# P10_USB_TO_UART0_IO_EXP_ADC.net
KiCad netlist of a schematic drawn in Altium Designer
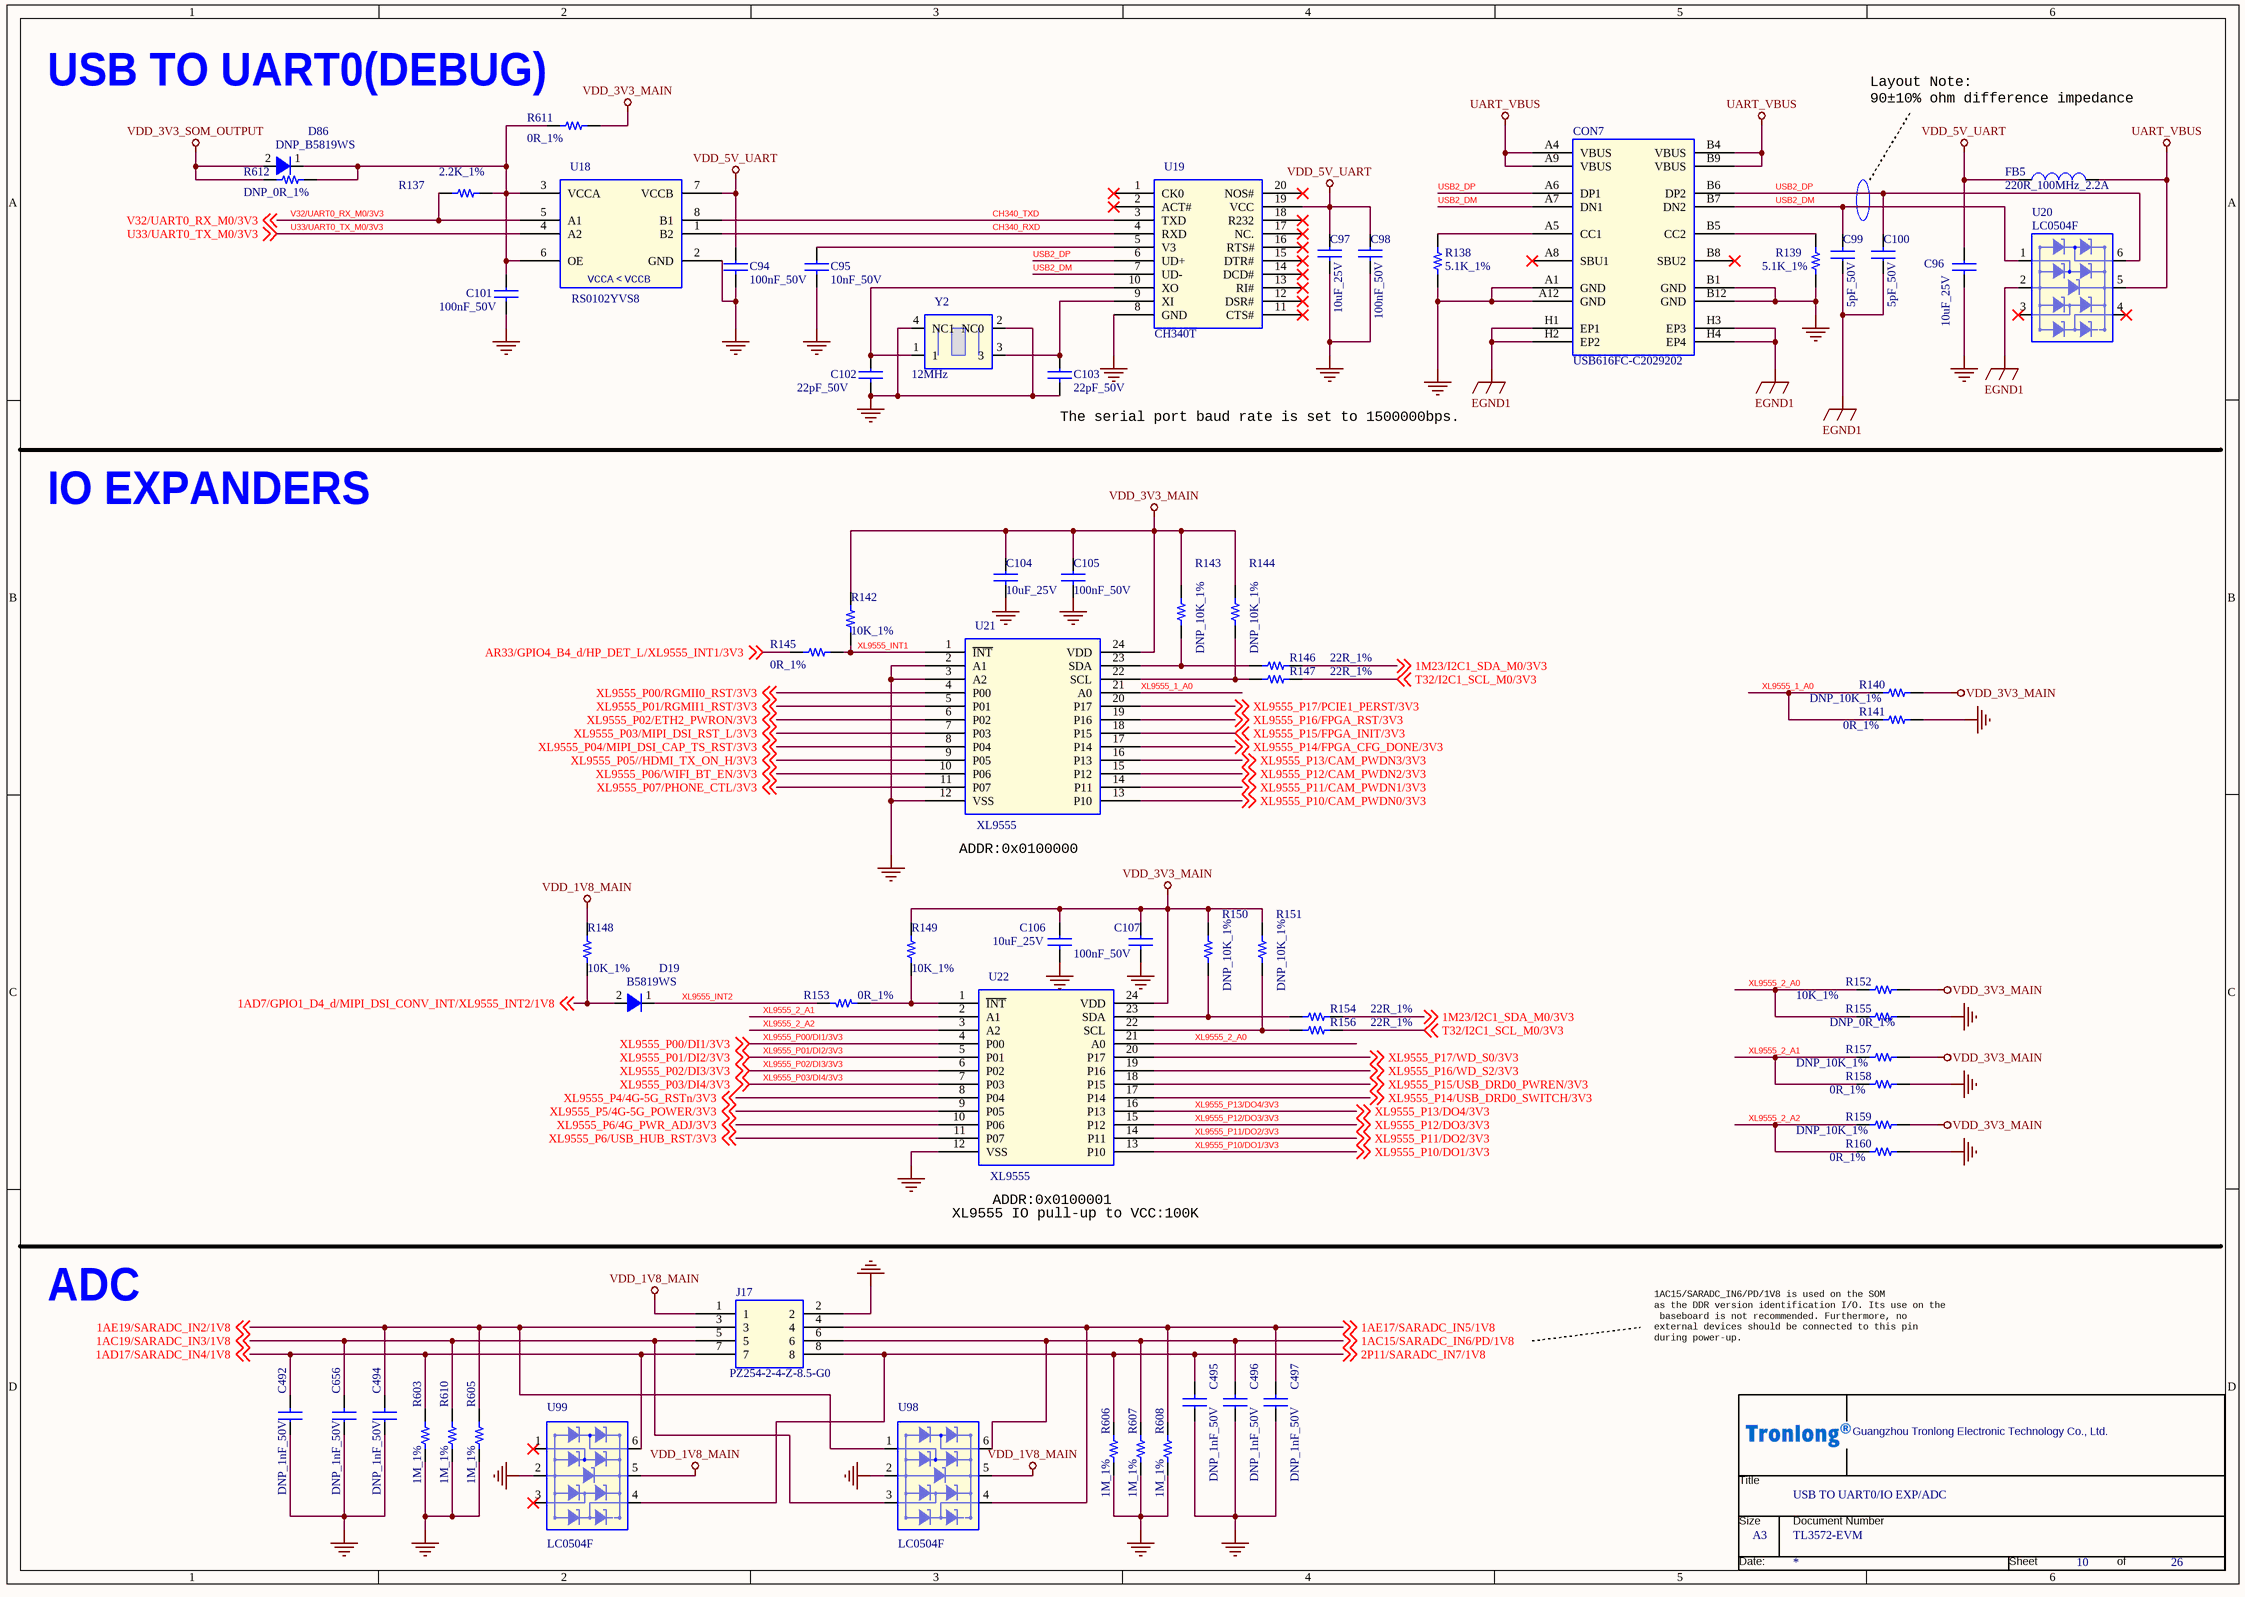
[diagram p0: P10_USB TO UART0_IO EXP_ADC.SchDoc]

(export (version "E")
  (design (tool "Eeschema 10.0.6"))
  (components
    (comp (ref "*")
      (value "Tronlong_TITTLE_20211115")
      (fields
        (field (name "DOC") "TL3572-EVM")
        (field (name "TITLE") "USB TO UART0/IO EXP/ADC")
        (field (name "ORGNAME") "Guangzhou Tronlong Electronic Technology Co., Ltd.")
        (field (name "PAGE SIZE") "A3")
        (field (name "PAGE NUMBER") "10")
        (field (name "PAGE COUNT") "26")
      )
      (libsource (lib "*") (part "Tronlong_TITTLE_20211115"))
    )
    (comp (ref "C94")
      (value "100nF_50V")
      (footprint "C0402")
      (description "贴片陶瓷电容,100nF,10%,50V,X7R")
      (fields
        (field (name "MANUFACTURER PARTNUMBER") "0402B104K500NT")
        (field (name "MANUFACTURER") "广东风华高新科技股份有限公司（FH）")
      )
      (libsource (lib "*") (part "CAP NP_Dup3"))
    )
    (comp (ref "C95")
      (value "10nF_50V")
      (footprint "C0402")
      (description "贴片陶瓷电容,10nF,10%,50V,X7R")
      (fields
        (field (name "MANUFACTURER PARTNUMBER") "0402B103K500NT")
        (field (name "MANUFACTURER") "广东风华高新科技股份有限公司（FH）")
      )
      (libsource (lib "*") (part "CAP NP_Dup3"))
    )
    (comp (ref "C96")
      (value "10uF_25V")
      (footprint "C0603")
      (description "贴片陶瓷电容,10uF,20%,25V,X5R")
      (fields
        (field (name "MANUFACTURER PARTNUMBER") "0603X106M250NT")
        (field (name "MANUFACTURER") "广东风华高新科技股份有限公司（FH）")
      )
      (libsource (lib "*") (part "CAP NP_Dup3"))
    )
    (comp (ref "C97")
      (value "10uF_25V")
      (footprint "C0603")
      (description "贴片陶瓷电容,10uF,20%,25V,X5R")
      (fields
        (field (name "MANUFACTURER") "广东风华高新科技股份有限公司（FH）")
        (field (name "MANUFACTURER PARTNUMBER") "0603X106M250NT")
      )
      (libsource (lib "*") (part "CAP NP_Dup3"))
    )
    (comp (ref "C98")
      (value "100nF_50V")
      (footprint "C0402")
      (description "贴片陶瓷电容,100nF,10%,50V,X7R")
      (fields
        (field (name "MANUFACTURER PARTNUMBER") "0402B104K500NT")
        (field (name "MANUFACTURER") "广东风华高新科技股份有限公司（FH）")
      )
      (libsource (lib "*") (part "CAP NP_Dup3"))
    )
    (comp (ref "C99")
      (value "5pF_50V")
      (footprint "C0402")
      (description "CC0402BRNPO9BN5R0")
      (fields
        (field (name "TOLERANCE") "±10%")
        (field (name "MANUFACTURER") "广州创龙")
        (field (name "CREATED BY") "JJJ")
      )
      (libsource (lib "*") (part "CAP NP_1"))
    )
    (comp (ref "C100")
      (value "5pF_50V")
      (footprint "C0402")
      (description "CC0402BRNPO9BN5R0")
      (fields
        (field (name "MANUFACTURER PARTNUMBER") "5pF,2%,C0402,50V,（NPO）")
        (field (name "MANUFACTURER") "广州创龙")
        (field (name "CREATED BY") "JJJ")
      )
      (libsource (lib "*") (part "CAP NP_1"))
    )
    (comp (ref "C101")
      (value "100nF_50V")
      (footprint "C0402")
      (description "贴片陶瓷电容,100nF,10%,50V,X7R")
      (fields
        (field (name "MANUFACTURER PARTNUMBER") "0402B104K500NT")
        (field (name "MANUFACTURER") "广东风华高新科技股份有限公司（FH）")
      )
      (libsource (lib "*") (part "CAP NP_Dup3"))
    )
    (comp (ref "C102")
      (value "22pF_50V")
      (footprint "C0603")
      (description "贴片陶瓷电容,22pF,5%,50V,COG")
      (fields
        (field (name "MANUFACTURER") "广东风华高新科技股份有限公司（FH）")
        (field (name "MANUFACTURER PARTNUMBER") "0603CG220J500NT")
      )
      (libsource (lib "*") (part "CAP NP_Dup3"))
    )
    (comp (ref "C103")
      (value "22pF_50V")
      (footprint "C0603")
      (description "贴片陶瓷电容,22pF,5%,50V,COG")
      (fields
        (field (name "MANUFACTURER") "广东风华高新科技股份有限公司（FH）")
        (field (name "MANUFACTURER PARTNUMBER") "0603CG220J500NT")
      )
      (libsource (lib "*") (part "CAP NP_Dup3"))
    )
    (comp (ref "C104")
      (value "10uF_25V")
      (footprint "C0603")
      (description "贴片陶瓷电容,4.7uF,10%,25V,X5R")
      (fields
        (field (name "MANUFACTURER") "广东风华高新科技股份有限公司（FH）")
        (field (name "MANUFACTURER PARTNUMBER") "0603X475K250NT")
      )
      (libsource (lib "*") (part "CAP NP_Dup3"))
    )
    (comp (ref "C105")
      (value "100nF_50V")
      (footprint "C0402")
      (description "贴片陶瓷电容,100nF,10%,50V,X7R")
      (fields
        (field (name "MANUFACTURER") "广东风华高新科技股份有限公司（FH）")
        (field (name "MANUFACTURER PARTNUMBER") "0402B104K500NT")
      )
      (libsource (lib "*") (part "CAP NP_Dup3"))
    )
    (comp (ref "C106")
      (value "10uF_25V")
      (footprint "C0603")
      (description "贴片陶瓷电容10uF,20%,25V,X5R")
      (fields
        (field (name "MANUFACTURER") "广东风华高新科技股份有限公司（FH）")
        (field (name "MANUFACTURER PARTNUMBER") "0603X106M250NT")
      )
      (libsource (lib "*") (part "CAP NP_Dup2"))
    )
    (comp (ref "C107")
      (value "100nF_50V")
      (footprint "C0402")
      (description "贴片陶瓷电容,100nF,10%,50V,X7R")
      (fields
        (field (name "MANUFACTURER PARTNUMBER") "0402B104K500NT")
        (field (name "MANUFACTURER") "广东风华高新科技股份有限公司（FH）")
      )
      (libsource (lib "*") (part "CAP NP_Dup2"))
    )
    (comp (ref "C492")
      (value "DNP_1nF_50V")
      (footprint "C0402")
      (description "贴片陶瓷电容,1nF,10%,50V,X7R")
      (fields
        (field (name "MANUFACTURER") "广东风华高新科技股份有限公司（FH）")
        (field (name "MANUFACTURER PARTNUMBER") "0402B102K500NT")
      )
      (libsource (lib "*") (part "CAP NP_Dup3"))
    )
    (comp (ref "C494")
      (value "DNP_1nF_50V")
      (footprint "C0402")
      (description "贴片陶瓷电容,1nF,10%,50V,X7R")
      (fields
        (field (name "MANUFACTURER") "广东风华高新科技股份有限公司（FH）")
        (field (name "MANUFACTURER PARTNUMBER") "0402B102K500NT")
      )
      (libsource (lib "*") (part "CAP NP_Dup3"))
    )
    (comp (ref "C495")
      (value "DNP_1nF_50V")
      (footprint "C0402")
      (description "贴片陶瓷电容,1nF,10%,50V,X7R")
      (fields
        (field (name "MANUFACTURER") "广东风华高新科技股份有限公司（FH）")
        (field (name "MANUFACTURER PARTNUMBER") "0402B102K500NT")
      )
      (libsource (lib "*") (part "CAP NP_Dup3"))
    )
    (comp (ref "C496")
      (value "DNP_1nF_50V")
      (footprint "C0402")
      (description "贴片陶瓷电容,1nF,10%,50V,X7R")
      (fields
        (field (name "MANUFACTURER") "广东风华高新科技股份有限公司（FH）")
        (field (name "MANUFACTURER PARTNUMBER") "0402B102K500NT")
      )
      (libsource (lib "*") (part "CAP NP_Dup3"))
    )
    (comp (ref "C497")
      (value "DNP_1nF_50V")
      (footprint "C0402")
      (description "贴片陶瓷电容,1nF,10%,50V,X7R")
      (fields
        (field (name "MANUFACTURER") "广东风华高新科技股份有限公司（FH）")
        (field (name "MANUFACTURER PARTNUMBER") "0402B102K500NT")
      )
      (libsource (lib "*") (part "CAP NP_Dup3"))
    )
    (comp (ref "C656")
      (value "DNP_1nF_50V")
      (footprint "C0402")
      (description "贴片陶瓷电容,1nF,10%,50V,X7R")
      (fields
        (field (name "PART NUMBER") "117-00-3036")
        (field (name "MANUFACTURER PARTNUMBER") "0402B102K500NT")
      )
      (libsource (lib "*") (part "CAP NP_Dup3"))
    )
    (comp (ref "CON7")
      (value "USB616FC-C2029202")
      (footprint "TYPE-C_16P_180_SMD")
      (description "Type-C座,16P,0.8mm,母座,侧贴")
      (fields (field (name "MANUFACTURER") "深圳市爱特姆科技有限公司（ATOM）"))
      (libsource (lib "*") (part "usb 3_0.0 type-c female"))
    )
    (comp (ref "D19")
      (value "B5819WS")
      (footprint "SOD-323")
      (description "肖特基二极管,VR=40V,IF=1A,VF=0.6V@1A")
      (fields (field (name "MFR") "On Semiconductor") (field (name "TIINTPARTNUMBER") "1E0013"))
      (libsource (lib "*") (part "Diode200mA250V_2"))
    )
    (comp (ref "D86")
      (value "DNP_B5819WS")
      (footprint "SOD-323")
      (description "肖特基二极管,VR=40V,IF=1A,VF=0.6V@1A")
      (fields (field (name "MFR") "On Semiconductor") (field (name "TIINTPARTNUMBER") "1E0013"))
      (libsource (lib "*") (part "Diode200mA250V_2"))
    )
    (comp (ref "FB5")
      (value "220R_100MHz_2.2A")
      (footprint "L0603")
      (description "磁珠,50mΩ,2.2A,220R@100MHz")
      (fields
        (field (name "MANUFACTURER") "深圳顺络电子股份有限公司（Sunlord）")
        (field (name "MANUFACTURER PARTNUMBER") "UPZ1608U221-2R2TF")
      )
      (libsource (lib "*") (part "FERRITE BEAD_0"))
    )
    (comp (ref "J17")
      (value "PZ254-2-4-Z-8.5-G0")
      (footprint "CON_2D54_2X4_TH")
      (description "插件双排排针,2x4P,2.54mm,针长L=11.5mm,180度")
      (fields (field (name "MANUFACTURER") "深圳市华灿天禄电子有限公司（HCTL)"))
      (libsource (lib "*") (part "PZ254-2-04-Z-8.5-G0"))
    )
    (comp (ref "R137")
      (value "2.2K_1%")
      (footprint "R0603")
      (description "贴片电阻,2.2K,±1%,1/10W")
      (fields
        (field (name "MANUFACTURER PARTNUMBER") "RS-03K2201FT")
        (field (name "MANUFACTURER") "广东风华高新科技股份有限公司（FH）")
      )
      (libsource (lib "*") (part "Resistor_Dup4"))
    )
    (comp (ref "R138")
      (value "5.1K_1%")
      (footprint "R0603")
      (description "RC0603FR-075K1L,0603WAF5101T5E")
      (fields
        (field (name "MANUFACTURER PARTNUMBER") "5.1K,±1%,R0603,≥1/10W")
        (field (name "MANUFACTURER") "广州创龙")
      )
      (libsource (lib "*") (part "Resistor_Dup4"))
    )
    (comp (ref "R139")
      (value "5.1K_1%")
      (footprint "R0603")
      (description "RC0603FR-075K1L,0603WAF5101T5E")
      (fields
        (field (name "MANUFACTURER") "广州创龙")
        (field (name "MANUFACTURER PARTNUMBER") "5.1K,±1%,R0603,≥1/10W")
      )
      (libsource (lib "*") (part "Resistor_Dup4"))
    )
    (comp (ref "R140")
      (value "DNP_10K_1%")
      (footprint "R0402")
      (description "贴片电阻,10K,±1%,1/16W")
      (fields
        (field (name "MANUFACTURER PARTNUMBER") "RC-02K1002FT")
        (field (name "MANUFACTURER") "广东风华高新科技股份有限公司（FH）")
      )
      (libsource (lib "*") (part "Resistor_Dup2"))
    )
    (comp (ref "R141")
      (value "0R_1%")
      (footprint "R0603")
      (description "贴片电阻,0R,±1%,1/10W")
      (fields
        (field (name "MANUFACTURER") "广东风华高新科技股份有限公司（FH）")
        (field (name "MANUFACTURER PARTNUMBER") "RS-03000FT")
      )
      (libsource (lib "*") (part "Resistor_Dup2"))
    )
    (comp (ref "R142")
      (value "10K_1%")
      (footprint "R0402")
      (description "贴片电阻,10K,±1%,1/16W")
      (fields
        (field (name "MANUFACTURER PARTNUMBER") "RC-02K1002FT")
        (field (name "MANUFACTURER") "广东风华高新科技股份有限公司（FH）")
      )
      (libsource (lib "*") (part "Resistor_Dup2"))
    )
    (comp (ref "R143")
      (value "DNP_10K_1%")
      (footprint "R0402")
      (description "贴片电阻,10K,±1%,1/16W")
      (fields
        (field (name "MANUFACTURER") "广东风华高新科技股份有限公司（FH）")
        (field (name "MANUFACTURER PARTNUMBER") "RC-02K1002FT")
      )
      (libsource (lib "*") (part "Resistor_Dup2"))
    )
    (comp (ref "R144")
      (value "DNP_10K_1%")
      (footprint "R0402")
      (description "贴片电阻,10K,±1%,1/16W")
      (fields
        (field (name "MANUFACTURER") "广东风华高新科技股份有限公司（FH）")
        (field (name "MANUFACTURER PARTNUMBER") "RC-02K1002FT")
      )
      (libsource (lib "*") (part "Resistor_Dup2"))
    )
    (comp (ref "R145")
      (value "0R_1%")
      (footprint "R0402")
      (description "贴片电阻,0R,±1%,1/16W")
      (fields
        (field (name "MANUFACTURER") "广东风华高新科技股份有限公司（FH）")
        (field (name "MANUFACTURER PARTNUMBER") "RC-02000FT")
      )
      (libsource (lib "*") (part "Resistor_Dup2"))
    )
    (comp (ref "R146")
      (value "22R_1%")
      (footprint "R0402")
      (description "贴片电阻,22R,±1%,1/16W")
      (fields
        (field (name "MANUFACTURER PARTNUMBER") "RC-02K22R0FT")
        (field (name "MANUFACTURER") "广东风华高新科技股份有限公司（FH）")
      )
      (libsource (lib "*") (part "Resistor_Dup2"))
    )
    (comp (ref "R147")
      (value "22R_1%")
      (footprint "R0402")
      (description "贴片电阻,22R,±1%,1/16W")
      (fields
        (field (name "MANUFACTURER PARTNUMBER") "RC-02K22R0FT")
        (field (name "MANUFACTURER") "广东风华高新科技股份有限公司（FH）")
      )
      (libsource (lib "*") (part "Resistor_Dup2"))
    )
    (comp (ref "R148")
      (value "10K_1%")
      (footprint "R0402")
      (description "贴片电阻,10K,±1%,1/16W")
      (fields
        (field (name "MANUFACTURER PARTNUMBER") "RC-02K1002FT")
        (field (name "MANUFACTURER") "广东风华高新科技股份有限公司（FH）")
      )
      (libsource (lib "*") (part "Resistor"))
    )
    (comp (ref "R149")
      (value "10K_1%")
      (footprint "R0402")
      (description "贴片电阻,10K,±1%,1/16W")
      (fields
        (field (name "MANUFACTURER PARTNUMBER") "RC-02K1002FT")
        (field (name "MANUFACTURER") "广东风华高新科技股份有限公司（FH）")
      )
      (libsource (lib "*") (part "Resistor"))
    )
    (comp (ref "R150")
      (value "DNP_10K_1%")
      (footprint "R0402")
      (description "贴片电阻,10K,±1%,1/16W")
      (fields
        (field (name "MANUFACTURER PARTNUMBER") "RC-02K1002FT")
        (field (name "MANUFACTURER") "广东风华高新科技股份有限公司（FH）")
      )
      (libsource (lib "*") (part "Resistor"))
    )
    (comp (ref "R151")
      (value "DNP_10K_1%")
      (footprint "R0402")
      (description "贴片电阻,10K,±1%,1/16W")
      (fields
        (field (name "MANUFACTURER") "广东风华高新科技股份有限公司（FH）")
        (field (name "MANUFACTURER PARTNUMBER") "RC-02K1002FT")
      )
      (libsource (lib "*") (part "Resistor"))
    )
    (comp (ref "R152")
      (value "10K_1%")
      (footprint "R0402")
      (description "贴片电阻,10K,±1%,1/16W")
      (fields
        (field (name "MANUFACTURER PARTNUMBER") "RC-02K1002FT")
        (field (name "MANUFACTURER") "广东风华高新科技股份有限公司（FH）")
      )
      (libsource (lib "*") (part "Resistor"))
    )
    (comp (ref "R153")
      (value "0R_1%")
      (footprint "R0402")
      (description "贴片电阻,0R,±1%,1/16W")
      (fields
        (field (name "MANUFACTURER") "广东风华高新科技股份有限公司（FH）")
        (field (name "MANUFACTURER PARTNUMBER") "RC-02000FT")
      )
      (libsource (lib "*") (part "Resistor"))
    )
    (comp (ref "R154")
      (value "22R_1%")
      (footprint "R0402")
      (description "贴片电阻,22R,±1%,1/16W")
      (fields
        (field (name "MANUFACTURER") "广东风华高新科技股份有限公司（FH）")
        (field (name "MANUFACTURER PARTNUMBER") "RC-02K22R0FT")
      )
      (libsource (lib "*") (part "Resistor"))
    )
    (comp (ref "R155")
      (value "DNP_0R_1%")
      (footprint "R0402")
      (description "贴片电阻,0R,±1%,1/16W")
      (fields
        (field (name "MANUFACTURER PARTNUMBER") "RC-02000FT")
        (field (name "MANUFACTURER") "广东风华高新科技股份有限公司（FH）")
      )
      (libsource (lib "*") (part "Resistor"))
    )
    (comp (ref "R156")
      (value "22R_1%")
      (footprint "R0402")
      (description "贴片电阻,22R,±1%,1/16W")
      (fields
        (field (name "MANUFACTURER") "广东风华高新科技股份有限公司（FH）")
        (field (name "MANUFACTURER PARTNUMBER") "RC-02K22R0FT")
      )
      (libsource (lib "*") (part "Resistor"))
    )
    (comp (ref "R157")
      (value "DNP_10K_1%")
      (footprint "R0402")
      (description "贴片电阻,10K,±1%,1/16W")
      (fields
        (field (name "MANUFACTURER PARTNUMBER") "RC-02K1002FT")
        (field (name "MANUFACTURER") "广东风华高新科技股份有限公司（FH）")
      )
      (libsource (lib "*") (part "Resistor"))
    )
    (comp (ref "R158")
      (value "0R_1%")
      (footprint "R0402")
      (description "贴片电阻,0R,±1%,1/16W")
      (fields
        (field (name "MANUFACTURER PARTNUMBER") "RC-02000FT")
        (field (name "MANUFACTURER") "广东风华高新科技股份有限公司（FH）")
      )
      (libsource (lib "*") (part "Resistor"))
    )
    (comp (ref "R159")
      (value "DNP_10K_1%")
      (footprint "R0402")
      (description "贴片电阻,10K,±1%,1/16W")
      (fields
        (field (name "MANUFACTURER PARTNUMBER") "RC-02K1002FT")
        (field (name "MANUFACTURER") "广东风华高新科技股份有限公司（FH）")
      )
      (libsource (lib "*") (part "Resistor"))
    )
    (comp (ref "R160")
      (value "0R_1%")
      (footprint "R0402")
      (description "贴片电阻,0R,±1%,1/16W")
      (fields
        (field (name "MANUFACTURER PARTNUMBER") "RC-02000FT")
        (field (name "MANUFACTURER") "广东风华高新科技股份有限公司（FH）")
      )
      (libsource (lib "*") (part "Resistor"))
    )
    (comp (ref "R603")
      (value "1M_1%")
      (footprint "R0603")
      (description "贴片电阻,1M,±1%,1/10W")
      (fields
        (field (name "MANUFACTURER PARTNUMBER") "RS-03K1004FT")
        (field (name "MANUFACTURER") "广东风华高新科技股份有限公司（FH）")
      )
      (libsource (lib "*") (part "Resistor_Dup3"))
    )
    (comp (ref "R605")
      (value "1M_1%")
      (footprint "R0603")
      (description "贴片电阻,1M,±1%,1/10W")
      (fields
        (field (name "MANUFACTURER PARTNUMBER") "RS-03K1004FT")
        (field (name "MANUFACTURER") "广东风华高新科技股份有限公司（FH）")
      )
      (libsource (lib "*") (part "Resistor_Dup3"))
    )
    (comp (ref "R606")
      (value "1M_1%")
      (footprint "R0603")
      (description "贴片电阻,1M,±1%,1/10W")
      (fields
        (field (name "MANUFACTURER") "广东风华高新科技股份有限公司（FH）")
        (field (name "MANUFACTURER PARTNUMBER") "RS-03K1004FT")
      )
      (libsource (lib "*") (part "Resistor_Dup3"))
    )
    (comp (ref "R607")
      (value "1M_1%")
      (footprint "R0603")
      (description "贴片电阻,1M,±1%,1/10W")
      (fields
        (field (name "MANUFACTURER PARTNUMBER") "RS-03K1004FT")
        (field (name "MANUFACTURER") "广东风华高新科技股份有限公司（FH）")
      )
      (libsource (lib "*") (part "Resistor_Dup3"))
    )
    (comp (ref "R608")
      (value "1M_1%")
      (footprint "R0603")
      (description "贴片电阻,1M,±1%,1/10W")
      (fields
        (field (name "MANUFACTURER") "广东风华高新科技股份有限公司（FH）")
        (field (name "MANUFACTURER PARTNUMBER") "RS-03K1004FT")
      )
      (libsource (lib "*") (part "Resistor_Dup3"))
    )
    (comp (ref "R610")
      (value "1M_1%")
      (footprint "R0603")
      (description "贴片电阻,1M,±1%,1/10W")
      (fields
        (field (name "MANUFACTURER PARTNUMBER") "RS-03K1004FT")
        (field (name "MANUFACTURER") "广东风华高新科技股份有限公司（FH）")
      )
      (libsource (lib "*") (part "Resistor_Dup3"))
    )
    (comp (ref "R611")
      (value "0R_1%")
      (footprint "R0402")
      (description "贴片电阻,0R,±1%,1/16W")
      (fields
        (field (name "MANUFACTURER PARTNUMBER") "RC-02000FT")
        (field (name "MANUFACTURER") "广东风华高新科技股份有限公司（FH）")
      )
      (libsource (lib "*") (part "Resistor_Dup2"))
    )
    (comp (ref "R612")
      (value "DNP_0R_1%")
      (footprint "R0402")
      (description "贴片电阻,0R,±1%,1/16W")
      (fields
        (field (name "MANUFACTURER PARTNUMBER") "RC-02000FT")
        (field (name "MANUFACTURER") "广东风华高新科技股份有限公司（FH）")
      )
      (libsource (lib "*") (part "Resistor_Dup2"))
    )
    (comp (ref "U18")
      (value "RS0102YVS8")
      (footprint "SOP8-20-91")
      (description "2位双向电平转换器")
      (fields (field (name "MANUFACTURER") "江苏润石科技有限公司（RUNIC）"))
      (libsource (lib "*") (part "TXS0102DCUR_0"))
    )
    (comp (ref "U19")
      (value "CH340T")
      (footprint "TSSOP-20")
      (description "USB转UART芯片")
      (fields (field (name "MANUFACTURER") "南京沁恒微电子股份有限公司（WCH）"))
      (libsource (lib "*") (part "CH340T"))
    )
    (comp (ref "U20")
      (value "LC0504F")
      (footprint "SOT363")
      (description "ESD二极管,VRWM=5V,VBR=6V,四组,单向,8KV,15KV")
      (fields (field (name "MANUFACTURER") "上海雷卯电子科技有限公司（Leiditech）"))
      (libsource (lib "*") (part "PRTR5V0U4Y"))
    )
    (comp (ref "U21")
      (value "XL9555")
      (footprint "TSSOP24")
      (description "拓展IO芯片")
      (fields (field (name "MANUFACTURER") "信路达信息技术（厦门）有限（xinluda）"))
      (libsource (lib "*") (part "XL9555_0"))
    )
    (comp (ref "U22")
      (value "XL9555")
      (footprint "TSSOP24")
      (description "拓展IO芯片")
      (fields (field (name "MANUFACTURER") "信路达信息技术（厦门）有限公司（xinluda）"))
      (libsource (lib "*") (part "XL9555_0"))
    )
    (comp (ref "U98")
      (value "LC0504F")
      (footprint "SOT363")
      (description "ESD二极管,VRWM=5V,VBR=6V,四组,单向,8KV,15KV")
      (fields (field (name "MANUFACTURER") "上海雷卯电子科技有限公司（Leiditech）"))
      (libsource (lib "*") (part "PRTR5V0U4Y"))
    )
    (comp (ref "U99")
      (value "LC0504F")
      (footprint "SOT363")
      (description "ESD二极管,VRWM=5V,VBR=6V,四组,单向,8KV,15KV")
      (fields (field (name "MANUFACTURER") "上海雷卯电子科技有限公司（Leiditech）"))
      (libsource (lib "*") (part "PRTR5V0U4Y"))
    )
    (comp (ref "Y2")
      (value "12MHz")
      (footprint "SMD_3225")
      (description "四脚无源晶振,12MHz,±10ppm,12pF,100Ω,±30ppm")
      (fields
        (field (name "MANUFACTURER") "深圳市星通时频电子有限公司（SCTF）")
        (field (name "MANUFACTURER PARTNUMBER") "S3B12.000F1210F30")
      )
      (libsource (lib "*") (part "CRYSTAL"))
    )
  )
  (nets
    (net (code "1") (name "/CH340_RXD") (class "Default")
      (node (ref "U18") (pin "1") (pinfunction "B2_1") (pintype "passive"))
      (node (ref "U19") (pin "4") (pinfunction "RXD_4") (pintype "passive"))
    )
    (net (code "2") (name "/CH340_TXD") (class "Default")
      (node (ref "U18") (pin "8") (pinfunction "B1_8") (pintype "passive"))
      (node (ref "U19") (pin "3") (pinfunction "TXD_3") (pintype "passive"))
    )
    (net (code "3") (name "/USB2_DM") (class "Default")
      (node (ref "C99") (pin "2") (pinfunction "2_2") (pintype "passive"))
      (node (ref "CON7") (pin "A7") (pinfunction "DN1_A7") (pintype "passive"))
      (node (ref "CON7") (pin "B7") (pinfunction "DN2_B7") (pintype "passive"))
      (node (ref "U19") (pin "7") (pinfunction "UD-_7") (pintype "passive"))
      (node (ref "U20") (pin "1") (pinfunction "1_1") (pintype "passive"))
    )
    (net (code "4") (name "/USB2_DP") (class "Default")
      (node (ref "C100") (pin "2") (pinfunction "2_2") (pintype "passive"))
      (node (ref "CON7") (pin "A6") (pinfunction "DP1_A6") (pintype "passive"))
      (node (ref "CON7") (pin "B6") (pinfunction "DP2_B6") (pintype "passive"))
      (node (ref "U19") (pin "6") (pinfunction "UD+_6") (pintype "passive"))
      (node (ref "U20") (pin "6") (pinfunction "6_6") (pintype "passive"))
    )
    (net (code "5") (name "/XL9555_1_A0") (class "Default")
      (node (ref "R140") (pin "2") (pinfunction "2_2") (pintype "passive"))
      (node (ref "R141") (pin "1") (pinfunction "1_1") (pintype "passive"))
      (node (ref "U21") (pin "21") (pinfunction "A0_21") (pintype "passive"))
    )
    (net (code "6") (name "/XL9555_2_A0") (class "Default")
      (node (ref "R152") (pin "2") (pinfunction "2_2") (pintype "passive"))
      (node (ref "R155") (pin "1") (pinfunction "1_1") (pintype "passive"))
      (node (ref "U22") (pin "21") (pinfunction "A0_21") (pintype "passive"))
    )
    (net (code "7") (name "/XL9555_2_A1") (class "Default")
      (node (ref "R157") (pin "2") (pinfunction "2_2") (pintype "passive"))
      (node (ref "R158") (pin "1") (pinfunction "1_1") (pintype "passive"))
      (node (ref "U22") (pin "2") (pinfunction "A1_2") (pintype "passive"))
    )
    (net (code "8") (name "/XL9555_2_A2") (class "Default")
      (node (ref "R159") (pin "2") (pinfunction "2_2") (pintype "passive"))
      (node (ref "R160") (pin "1") (pinfunction "1_1") (pintype "passive"))
      (node (ref "U22") (pin "3") (pinfunction "A2_3") (pintype "passive"))
    )
    (net (code "9") (name "/XL9555_INT1") (class "Default")
      (node (ref "R142") (pin "2") (pinfunction "2_2") (pintype "passive"))
      (node (ref "R145") (pin "2") (pinfunction "2_2") (pintype "passive"))
      (node (ref "U21") (pin "1") (pinfunction "~{INT}_1") (pintype "passive"))
    )
    (net (code "10") (name "/XL9555_INT2") (class "Default")
      (node (ref "D19") (pin "1") (pinfunction "Anode_1") (pintype "passive"))
      (node (ref "R153") (pin "1") (pinfunction "1_1") (pintype "passive"))
    )
    (net (code "11") (name "1AC15{slash}SARADC_IN6{slash}PD{slash}1V8") (class "Default")
      (node (ref "C496") (pin "2") (pinfunction "2_2") (pintype "passive"))
      (node (ref "J17") (pin "6") (pinfunction "6_6") (pintype "passive"))
      (node (ref "R607") (pin "1") (pinfunction "1_1") (pintype "passive"))
      (node (ref "U98") (pin "6") (pinfunction "6_6") (pintype "passive"))
    )
    (net (code "12") (name "1AC19{slash}SARADC_IN3{slash}1V8") (class "Default")
      (node (ref "C656") (pin "2") (pinfunction "2_2") (pintype "passive"))
      (node (ref "J17") (pin "5") (pinfunction "5_5") (pintype "passive"))
      (node (ref "R610") (pin "1") (pinfunction "1_1") (pintype "passive"))
      (node (ref "U98") (pin "3") (pinfunction "3_3") (pintype "passive"))
    )
    (net (code "13") (name "1AD7{slash}GPIO1_D4_d{slash}MIPI_DSI_CONV_INT{slash}XL9555_INT2{slash}1V8") (class "Default")
      (node (ref "D19") (pin "2") (pinfunction "Cathode_2") (pintype "passive"))
      (node (ref "R148") (pin "2") (pinfunction "2_2") (pintype "passive"))
    )
    (net (code "14") (name "1AD17{slash}SARADC_IN4{slash}1V8") (class "Default")
      (node (ref "C492") (pin "2") (pinfunction "2_2") (pintype "passive"))
      (node (ref "J17") (pin "7") (pinfunction "7_7") (pintype "passive"))
      (node (ref "R603") (pin "1") (pinfunction "1_1") (pintype "passive"))
      (node (ref "U99") (pin "6") (pinfunction "6_6") (pintype "passive"))
    )
    (net (code "15") (name "1AE17{slash}SARADC_IN5{slash}1V8") (class "Default")
      (node (ref "C497") (pin "2") (pinfunction "2_2") (pintype "passive"))
      (node (ref "J17") (pin "4") (pinfunction "4_4") (pintype "passive"))
      (node (ref "R608") (pin "1") (pinfunction "1_1") (pintype "passive"))
      (node (ref "U98") (pin "4") (pinfunction "4_4") (pintype "passive"))
    )
    (net (code "16") (name "1AE19{slash}SARADC_IN2{slash}1V8") (class "Default")
      (node (ref "C494") (pin "2") (pinfunction "2_2") (pintype "passive"))
      (node (ref "J17") (pin "3") (pinfunction "3_3") (pintype "passive"))
      (node (ref "R605") (pin "1") (pinfunction "1_1") (pintype "passive"))
      (node (ref "U98") (pin "1") (pinfunction "1_1") (pintype "passive"))
    )
    (net (code "17") (name "1M23{slash}I2C1_SDA_M0{slash}3V3") (class "Default")
      (node (ref "R146") (pin "1") (pinfunction "1_1") (pintype "passive"))
      (node (ref "R154") (pin "1") (pinfunction "1_1") (pintype "passive"))
    )
    (net (code "18") (name "2P11{slash}SARADC_IN7{slash}1V8") (class "Default")
      (node (ref "C495") (pin "2") (pinfunction "2_2") (pintype "passive"))
      (node (ref "J17") (pin "8") (pinfunction "8_8") (pintype "passive"))
      (node (ref "R606") (pin "1") (pinfunction "1_1") (pintype "passive"))
      (node (ref "U99") (pin "4") (pinfunction "4_4") (pintype "passive"))
    )
    (net (code "19") (name "AR33{slash}GPIO4_B4_d{slash}HP_DET_L{slash}XL9555_INT1{slash}3V3") (class "Default")
      (node (ref "R145") (pin "1") (pinfunction "1_1") (pintype "passive"))
    )
    (net (code "20") (name "EGND1") (class "Default")
      (node (ref "C100") (pin "1") (pinfunction "1_1") (pintype "passive"))
      (node (ref "C99") (pin "1") (pinfunction "1_1") (pintype "passive"))
      (node (ref "CON7") (pin "H1") (pinfunction "EP1_H1") (pintype "power_in"))
      (node (ref "CON7") (pin "H2") (pinfunction "EP2_H2") (pintype "power_in"))
      (node (ref "CON7") (pin "H3") (pinfunction "EP3_H3") (pintype "power_in"))
      (node (ref "CON7") (pin "H4") (pinfunction "EP4_H4") (pintype "power_in"))
      (node (ref "U20") (pin "2") (pinfunction "2_2") (pintype "passive"))
    )
    (net (code "21") (name "GND") (class "Default")
      (node (ref "C101") (pin "2") (pinfunction "2_2") (pintype "passive"))
      (node (ref "C102") (pin "2") (pinfunction "2_2") (pintype "passive"))
      (node (ref "C103") (pin "2") (pinfunction "2_2") (pintype "passive"))
      (node (ref "C104") (pin "2") (pinfunction "2_2") (pintype "passive"))
      (node (ref "C105") (pin "2") (pinfunction "2_2") (pintype "passive"))
      (node (ref "C106") (pin "2") (pinfunction "2_2") (pintype "passive"))
      (node (ref "C107") (pin "2") (pinfunction "2_2") (pintype "passive"))
      (node (ref "C492") (pin "1") (pinfunction "1_1") (pintype "passive"))
      (node (ref "C494") (pin "1") (pinfunction "1_1") (pintype "passive"))
      (node (ref "C495") (pin "1") (pinfunction "1_1") (pintype "passive"))
      (node (ref "C496") (pin "1") (pinfunction "1_1") (pintype "passive"))
      (node (ref "C497") (pin "1") (pinfunction "1_1") (pintype "passive"))
      (node (ref "C656") (pin "1") (pinfunction "1_1") (pintype "passive"))
      (node (ref "C94") (pin "2") (pinfunction "2_2") (pintype "passive"))
      (node (ref "C95") (pin "2") (pinfunction "2_2") (pintype "passive"))
      (node (ref "C96") (pin "2") (pinfunction "2_2") (pintype "passive"))
      (node (ref "C97") (pin "2") (pinfunction "2_2") (pintype "passive"))
      (node (ref "C98") (pin "2") (pinfunction "2_2") (pintype "passive"))
      (node (ref "CON7") (pin "A1") (pinfunction "GND_A1") (pintype "power_in"))
      (node (ref "CON7") (pin "A12") (pinfunction "GND_A12") (pintype "power_in"))
      (node (ref "CON7") (pin "B1") (pinfunction "GND_B1") (pintype "power_in"))
      (node (ref "CON7") (pin "B12") (pinfunction "GND_B12") (pintype "power_in"))
      (node (ref "J17") (pin "2") (pinfunction "2_2") (pintype "passive"))
      (node (ref "R138") (pin "2") (pinfunction "2_2") (pintype "passive"))
      (node (ref "R139") (pin "2") (pinfunction "2_2") (pintype "passive"))
      (node (ref "R141") (pin "2") (pinfunction "2_2") (pintype "passive"))
      (node (ref "R155") (pin "2") (pinfunction "2_2") (pintype "passive"))
      (node (ref "R158") (pin "2") (pinfunction "2_2") (pintype "passive"))
      (node (ref "R160") (pin "2") (pinfunction "2_2") (pintype "passive"))
      (node (ref "R603") (pin "2") (pinfunction "2_2") (pintype "passive"))
      (node (ref "R605") (pin "2") (pinfunction "2_2") (pintype "passive"))
      (node (ref "R606") (pin "2") (pinfunction "2_2") (pintype "passive"))
      (node (ref "R607") (pin "2") (pinfunction "2_2") (pintype "passive"))
      (node (ref "R608") (pin "2") (pinfunction "2_2") (pintype "passive"))
      (node (ref "R610") (pin "2") (pinfunction "2_2") (pintype "passive"))
      (node (ref "U18") (pin "2") (pinfunction "GND_2") (pintype "passive"))
      (node (ref "U19") (pin "8") (pinfunction "GND_8") (pintype "passive"))
      (node (ref "U21") (pin "12") (pinfunction "VSS_12") (pintype "passive"))
      (node (ref "U21") (pin "2") (pinfunction "A1_2") (pintype "passive"))
      (node (ref "U21") (pin "3") (pinfunction "A2_3") (pintype "passive"))
      (node (ref "U22") (pin "12") (pinfunction "VSS_12") (pintype "passive"))
      (node (ref "U98") (pin "2") (pinfunction "2_2") (pintype "passive"))
      (node (ref "U99") (pin "2") (pinfunction "2_2") (pintype "passive"))
      (node (ref "Y2") (pin "2") (pinfunction "NC0_2") (pintype "passive"))
      (node (ref "Y2") (pin "4") (pinfunction "NC1_4") (pintype "passive"))
    )
    (net (code "22") (name "Net-(CON7-CC1)") (class "Default")
      (node (ref "CON7") (pin "A5") (pinfunction "CC1_A5") (pintype "passive"))
      (node (ref "R138") (pin "1") (pinfunction "1_1") (pintype "passive"))
    )
    (net (code "23") (name "Net-(CON7-CC2)") (class "Default")
      (node (ref "CON7") (pin "B5") (pinfunction "CC2_B5") (pintype "passive"))
      (node (ref "R139") (pin "1") (pinfunction "1_1") (pintype "passive"))
    )
    (net (code "24") (name "Net-(D86-Anode)") (class "Default")
      (node (ref "C101") (pin "1") (pinfunction "1_1") (pintype "passive"))
      (node (ref "D86") (pin "1") (pinfunction "Anode_1") (pintype "passive"))
      (node (ref "R137") (pin "2") (pinfunction "2_2") (pintype "passive"))
      (node (ref "R611") (pin "1") (pinfunction "1_1") (pintype "passive"))
      (node (ref "R612") (pin "2") (pinfunction "2_2") (pintype "passive"))
      (node (ref "U18") (pin "3") (pinfunction "VCCA_3") (pintype "passive"))
      (node (ref "U18") (pin "6") (pinfunction "OE_6") (pintype "passive"))
    )
    (net (code "25") (name "Net-(U19-V3)") (class "Default")
      (node (ref "C95") (pin "1") (pinfunction "1_1") (pintype "passive"))
      (node (ref "U19") (pin "5") (pinfunction "V3_5") (pintype "passive"))
    )
    (net (code "26") (name "Net-(U19-XI)") (class "Default")
      (node (ref "C103") (pin "1") (pinfunction "1_1") (pintype "passive"))
      (node (ref "U19") (pin "9") (pinfunction "XI_9") (pintype "passive"))
      (node (ref "Y2") (pin "3") (pinfunction "3_3") (pintype "passive"))
    )
    (net (code "27") (name "Net-(U19-XO)") (class "Default")
      (node (ref "C102") (pin "1") (pinfunction "1_1") (pintype "passive"))
      (node (ref "U19") (pin "10") (pinfunction "XO_10") (pintype "passive"))
      (node (ref "Y2") (pin "1") (pinfunction "1_1") (pintype "passive"))
    )
    (net (code "28") (name "Net-(U21-SCL)") (class "Default")
      (node (ref "R144") (pin "2") (pinfunction "2_2") (pintype "passive"))
      (node (ref "R147") (pin "2") (pinfunction "2_2") (pintype "passive"))
      (node (ref "U21") (pin "22") (pinfunction "SCL_22") (pintype "passive"))
    )
    (net (code "29") (name "Net-(U21-SDA)") (class "Default")
      (node (ref "R143") (pin "2") (pinfunction "2_2") (pintype "passive"))
      (node (ref "R146") (pin "2") (pinfunction "2_2") (pintype "passive"))
      (node (ref "U21") (pin "23") (pinfunction "SDA_23") (pintype "passive"))
    )
    (net (code "30") (name "Net-(U22-SCL)") (class "Default")
      (node (ref "R151") (pin "2") (pinfunction "2_2") (pintype "passive"))
      (node (ref "R156") (pin "2") (pinfunction "2_2") (pintype "passive"))
      (node (ref "U22") (pin "22") (pinfunction "SCL_22") (pintype "passive"))
    )
    (net (code "31") (name "Net-(U22-SDA)") (class "Default")
      (node (ref "R150") (pin "2") (pinfunction "2_2") (pintype "passive"))
      (node (ref "R154") (pin "2") (pinfunction "2_2") (pintype "passive"))
      (node (ref "U22") (pin "23") (pinfunction "SDA_23") (pintype "passive"))
    )
    (net (code "32") (name "Net-(U22-~{INT})") (class "Default")
      (node (ref "R149") (pin "2") (pinfunction "2_2") (pintype "passive"))
      (node (ref "R153") (pin "2") (pinfunction "2_2") (pintype "passive"))
      (node (ref "U22") (pin "1") (pinfunction "~{INT}_1") (pintype "passive"))
    )
    (net (code "33") (name "T32{slash}I2C1_SCL_M0{slash}3V3") (class "Default")
      (node (ref "R147") (pin "1") (pinfunction "1_1") (pintype "passive"))
      (node (ref "R156") (pin "1") (pinfunction "1_1") (pintype "passive"))
    )
    (net (code "34") (name "U33{slash}UART0_TX_M0{slash}3V3") (class "Default")
      (node (ref "U18") (pin "4") (pinfunction "A2_4") (pintype "passive"))
    )
    (net (code "35") (name "UART_VBUS") (class "Default")
      (node (ref "CON7") (pin "A4") (pinfunction "VBUS_A4") (pintype "power_in"))
      (node (ref "CON7") (pin "A9") (pinfunction "VBUS_A9") (pintype "power_in"))
      (node (ref "CON7") (pin "B4") (pinfunction "VBUS_B4") (pintype "power_in"))
      (node (ref "CON7") (pin "B9") (pinfunction "VBUS_B9") (pintype "power_in"))
      (node (ref "FB5") (pin "2") (pinfunction "2_2") (pintype "passive"))
      (node (ref "U20") (pin "5") (pinfunction "5_5") (pintype "passive"))
    )
    (net (code "36") (name "V32{slash}UART0_RX_M0{slash}3V3") (class "Default")
      (node (ref "R137") (pin "1") (pinfunction "1_1") (pintype "passive"))
      (node (ref "U18") (pin "5") (pinfunction "A1_5") (pintype "passive"))
    )
    (net (code "37") (name "VDD_1V8_MAIN") (class "Default")
      (node (ref "J17") (pin "1") (pinfunction "1_1") (pintype "passive"))
      (node (ref "R148") (pin "1") (pinfunction "1_1") (pintype "passive"))
      (node (ref "U98") (pin "5") (pinfunction "5_5") (pintype "passive"))
      (node (ref "U99") (pin "5") (pinfunction "5_5") (pintype "passive"))
    )
    (net (code "38") (name "VDD_3V3_MAIN") (class "Default")
      (node (ref "C104") (pin "1") (pinfunction "1_1") (pintype "passive"))
      (node (ref "C105") (pin "1") (pinfunction "1_1") (pintype "passive"))
      (node (ref "C106") (pin "1") (pinfunction "1_1") (pintype "passive"))
      (node (ref "C107") (pin "1") (pinfunction "1_1") (pintype "passive"))
      (node (ref "R140") (pin "1") (pinfunction "1_1") (pintype "passive"))
      (node (ref "R142") (pin "1") (pinfunction "1_1") (pintype "passive"))
      (node (ref "R143") (pin "1") (pinfunction "1_1") (pintype "passive"))
      (node (ref "R144") (pin "1") (pinfunction "1_1") (pintype "passive"))
      (node (ref "R149") (pin "1") (pinfunction "1_1") (pintype "passive"))
      (node (ref "R150") (pin "1") (pinfunction "1_1") (pintype "passive"))
      (node (ref "R151") (pin "1") (pinfunction "1_1") (pintype "passive"))
      (node (ref "R152") (pin "1") (pinfunction "1_1") (pintype "passive"))
      (node (ref "R157") (pin "1") (pinfunction "1_1") (pintype "passive"))
      (node (ref "R159") (pin "1") (pinfunction "1_1") (pintype "passive"))
      (node (ref "R611") (pin "2") (pinfunction "2_2") (pintype "passive"))
      (node (ref "U21") (pin "24") (pinfunction "VDD_24") (pintype "passive"))
      (node (ref "U22") (pin "24") (pinfunction "VDD_24") (pintype "passive"))
    )
    (net (code "39") (name "VDD_3V3_SOM_OUTPUT") (class "Default")
      (node (ref "D86") (pin "2") (pinfunction "Cathode_2") (pintype "passive"))
      (node (ref "R612") (pin "1") (pinfunction "1_1") (pintype "passive"))
    )
    (net (code "40") (name "VDD_5V_UART") (class "Default")
      (node (ref "C94") (pin "1") (pinfunction "1_1") (pintype "passive"))
      (node (ref "C96") (pin "1") (pinfunction "1_1") (pintype "passive"))
      (node (ref "C97") (pin "1") (pinfunction "1_1") (pintype "passive"))
      (node (ref "C98") (pin "1") (pinfunction "1_1") (pintype "passive"))
      (node (ref "FB5") (pin "1") (pinfunction "1_1") (pintype "passive"))
      (node (ref "U18") (pin "7") (pinfunction "VCCB_7") (pintype "passive"))
      (node (ref "U19") (pin "19") (pinfunction "VCC_19") (pintype "passive"))
    )
    (net (code "41") (name "XL9555_P00{slash}DI1{slash}3V3") (class "Default")
      (node (ref "U22") (pin "4") (pinfunction "P00_4") (pintype "passive"))
    )
    (net (code "42") (name "XL9555_P00{slash}RGMII0_RST{slash}3V3") (class "Default")
      (node (ref "U21") (pin "4") (pinfunction "P00_4") (pintype "passive"))
    )
    (net (code "43") (name "XL9555_P01{slash}DI2{slash}3V3") (class "Default")
      (node (ref "U22") (pin "5") (pinfunction "P01_5") (pintype "passive"))
    )
    (net (code "44") (name "XL9555_P01{slash}RGMII1_RST{slash}3V3") (class "Default")
      (node (ref "U21") (pin "5") (pinfunction "P01_5") (pintype "passive"))
    )
    (net (code "45") (name "XL9555_P02{slash}DI3{slash}3V3") (class "Default")
      (node (ref "U22") (pin "6") (pinfunction "P02_6") (pintype "passive"))
    )
    (net (code "46") (name "XL9555_P02{slash}ETH2_PWRON{slash}3V3") (class "Default")
      (node (ref "U21") (pin "6") (pinfunction "P02_6") (pintype "passive"))
    )
    (net (code "47") (name "XL9555_P03{slash}DI4{slash}3V3") (class "Default")
      (node (ref "U22") (pin "7") (pinfunction "P03_7") (pintype "passive"))
    )
    (net (code "48") (name "XL9555_P03{slash}MIPI_DSI_RST_L{slash}3V3") (class "Default")
      (node (ref "U21") (pin "7") (pinfunction "P03_7") (pintype "passive"))
    )
    (net (code "49") (name "XL9555_P4{slash}4G-5G_RSTn{slash}3V3") (class "Default")
      (node (ref "U22") (pin "8") (pinfunction "P04_8") (pintype "passive"))
    )
    (net (code "50") (name "XL9555_P04{slash}MIPI_DSI_CAP_TS_RST{slash}3V3") (class "Default")
      (node (ref "U21") (pin "8") (pinfunction "P04_8") (pintype "passive"))
    )
    (net (code "51") (name "XL9555_P5{slash}4G-5G_POWER{slash}3V3") (class "Default")
      (node (ref "U22") (pin "9") (pinfunction "P05_9") (pintype "passive"))
    )
    (net (code "52") (name "XL9555_P05{slash}{slash}HDMI_TX_ON_H{slash}3V3") (class "Default")
      (node (ref "U21") (pin "9") (pinfunction "P05_9") (pintype "passive"))
    )
    (net (code "53") (name "XL9555_P6{slash}4G_PWR_ADJ{slash}3V3") (class "Default")
      (node (ref "U22") (pin "10") (pinfunction "P06_10") (pintype "passive"))
    )
    (net (code "54") (name "XL9555_P6{slash}USB_HUB_RST{slash}3V3") (class "Default")
      (node (ref "U22") (pin "11") (pinfunction "P07_11") (pintype "passive"))
    )
    (net (code "55") (name "XL9555_P06{slash}WIFI_BT_EN{slash}3V3") (class "Default")
      (node (ref "U21") (pin "10") (pinfunction "P06_10") (pintype "passive"))
    )
    (net (code "56") (name "XL9555_P07{slash}PHONE_CTL{slash}3V3") (class "Default")
      (node (ref "U21") (pin "11") (pinfunction "P07_11") (pintype "passive"))
    )
    (net (code "57") (name "XL9555_P10{slash}CAM_PWDN0{slash}3V3") (class "Default")
      (node (ref "U21") (pin "13") (pinfunction "P10_13") (pintype "passive"))
    )
    (net (code "58") (name "XL9555_P10{slash}DO1{slash}3V3") (class "Default")
      (node (ref "U22") (pin "13") (pinfunction "P10_13") (pintype "passive"))
    )
    (net (code "59") (name "XL9555_P11{slash}CAM_PWDN1{slash}3V3") (class "Default")
      (node (ref "U21") (pin "14") (pinfunction "P11_14") (pintype "passive"))
    )
    (net (code "60") (name "XL9555_P11{slash}DO2{slash}3V3") (class "Default")
      (node (ref "U22") (pin "14") (pinfunction "P11_14") (pintype "passive"))
    )
    (net (code "61") (name "XL9555_P12{slash}CAM_PWDN2{slash}3V3") (class "Default")
      (node (ref "U21") (pin "15") (pinfunction "P12_15") (pintype "passive"))
    )
    (net (code "62") (name "XL9555_P12{slash}DO3{slash}3V3") (class "Default")
      (node (ref "U22") (pin "15") (pinfunction "P12_15") (pintype "passive"))
    )
    (net (code "63") (name "XL9555_P13{slash}CAM_PWDN3{slash}3V3") (class "Default")
      (node (ref "U21") (pin "16") (pinfunction "P13_16") (pintype "passive"))
    )
    (net (code "64") (name "XL9555_P13{slash}DO4{slash}3V3") (class "Default")
      (node (ref "U22") (pin "16") (pinfunction "P13_16") (pintype "passive"))
    )
    (net (code "65") (name "XL9555_P14{slash}FPGA_CFG_DONE{slash}3V3") (class "Default")
      (node (ref "U21") (pin "17") (pinfunction "P14_17") (pintype "passive"))
    )
    (net (code "66") (name "XL9555_P14{slash}USB_DRD0_SWITCH{slash}3V3") (class "Default")
      (node (ref "U22") (pin "17") (pinfunction "P14_17") (pintype "passive"))
    )
    (net (code "67") (name "XL9555_P15{slash}FPGA_INIT{slash}3V3") (class "Default")
      (node (ref "U21") (pin "18") (pinfunction "P15_18") (pintype "passive"))
    )
    (net (code "68") (name "XL9555_P15{slash}USB_DRD0_PWREN{slash}3V3") (class "Default")
      (node (ref "U22") (pin "18") (pinfunction "P15_18") (pintype "passive"))
    )
    (net (code "69") (name "XL9555_P16{slash}FPGA_RST{slash}3V3") (class "Default")
      (node (ref "U21") (pin "19") (pinfunction "P16_19") (pintype "passive"))
    )
    (net (code "70") (name "XL9555_P16{slash}WD_S2{slash}3V3") (class "Default")
      (node (ref "U22") (pin "19") (pinfunction "P16_19") (pintype "passive"))
    )
    (net (code "71") (name "XL9555_P17{slash}PCIE1_PERST{slash}3V3") (class "Default")
      (node (ref "U21") (pin "20") (pinfunction "P17_20") (pintype "passive"))
    )
    (net (code "72") (name "XL9555_P17{slash}WD_S0{slash}3V3") (class "Default")
      (node (ref "U22") (pin "20") (pinfunction "P17_20") (pintype "passive"))
    )
    (net (code "73") (name "unconnected-(CON7-SBU1-PadA8)") (class "Default")
      (node (ref "CON7") (pin "A8") (pinfunction "SBU1_A8") (pintype "passive+no_connect"))
    )
    (net (code "74") (name "unconnected-(CON7-SBU2-PadB8)") (class "Default")
      (node (ref "CON7") (pin "B8") (pinfunction "SBU2_B8") (pintype "passive+no_connect"))
    )
    (net (code "75") (name "unconnected-(U19-ACT#-Pad2)") (class "Default")
      (node (ref "U19") (pin "2") (pinfunction "ACT#_2") (pintype "passive+no_connect"))
    )
    (net (code "76") (name "unconnected-(U19-CK0-Pad1)") (class "Default")
      (node (ref "U19") (pin "1") (pinfunction "CK0_1") (pintype "passive+no_connect"))
    )
    (net (code "77") (name "unconnected-(U19-CTS#-Pad11)") (class "Default")
      (node (ref "U19") (pin "11") (pinfunction "CTS#_11") (pintype "passive+no_connect"))
    )
    (net (code "78") (name "unconnected-(U19-DCD#-Pad14)") (class "Default")
      (node (ref "U19") (pin "14") (pinfunction "DCD#_14") (pintype "passive+no_connect"))
    )
    (net (code "79") (name "unconnected-(U19-DSR#-Pad12)") (class "Default")
      (node (ref "U19") (pin "12") (pinfunction "DSR#_12") (pintype "passive+no_connect"))
    )
    (net (code "80") (name "unconnected-(U19-DTR#-Pad15)") (class "Default")
      (node (ref "U19") (pin "15") (pinfunction "DTR#_15") (pintype "passive+no_connect"))
    )
    (net (code "81") (name "unconnected-(U19-NC.-Pad17)") (class "Default")
      (node (ref "U19") (pin "17") (pinfunction "NC._17") (pintype "passive+no_connect"))
    )
    (net (code "82") (name "unconnected-(U19-NOS#-Pad20)") (class "Default")
      (node (ref "U19") (pin "20") (pinfunction "NOS#_20") (pintype "passive+no_connect"))
    )
    (net (code "83") (name "unconnected-(U19-R232-Pad18)") (class "Default")
      (node (ref "U19") (pin "18") (pinfunction "R232_18") (pintype "passive+no_connect"))
    )
    (net (code "84") (name "unconnected-(U19-RI#-Pad13)") (class "Default")
      (node (ref "U19") (pin "13") (pinfunction "RI#_13") (pintype "passive+no_connect"))
    )
    (net (code "85") (name "unconnected-(U19-RTS#-Pad16)") (class "Default")
      (node (ref "U19") (pin "16") (pinfunction "RTS#_16") (pintype "passive+no_connect"))
    )
    (net (code "86") (name "unconnected-(U20-Pad3)") (class "Default")
      (node (ref "U20") (pin "3") (pinfunction "3_3") (pintype "passive+no_connect"))
    )
    (net (code "87") (name "unconnected-(U20-Pad4)") (class "Default")
      (node (ref "U20") (pin "4") (pinfunction "4_4") (pintype "passive+no_connect"))
    )
    (net (code "88") (name "unconnected-(U99-Pad1)") (class "Default")
      (node (ref "U99") (pin "1") (pinfunction "1_1") (pintype "passive+no_connect"))
    )
    (net (code "89") (name "unconnected-(U99-Pad3)") (class "Default")
      (node (ref "U99") (pin "3") (pinfunction "3_3") (pintype "passive+no_connect"))
    )
  )
)
